# fpga.net
KiCad netlist of a schematic drawn in Altium Designer
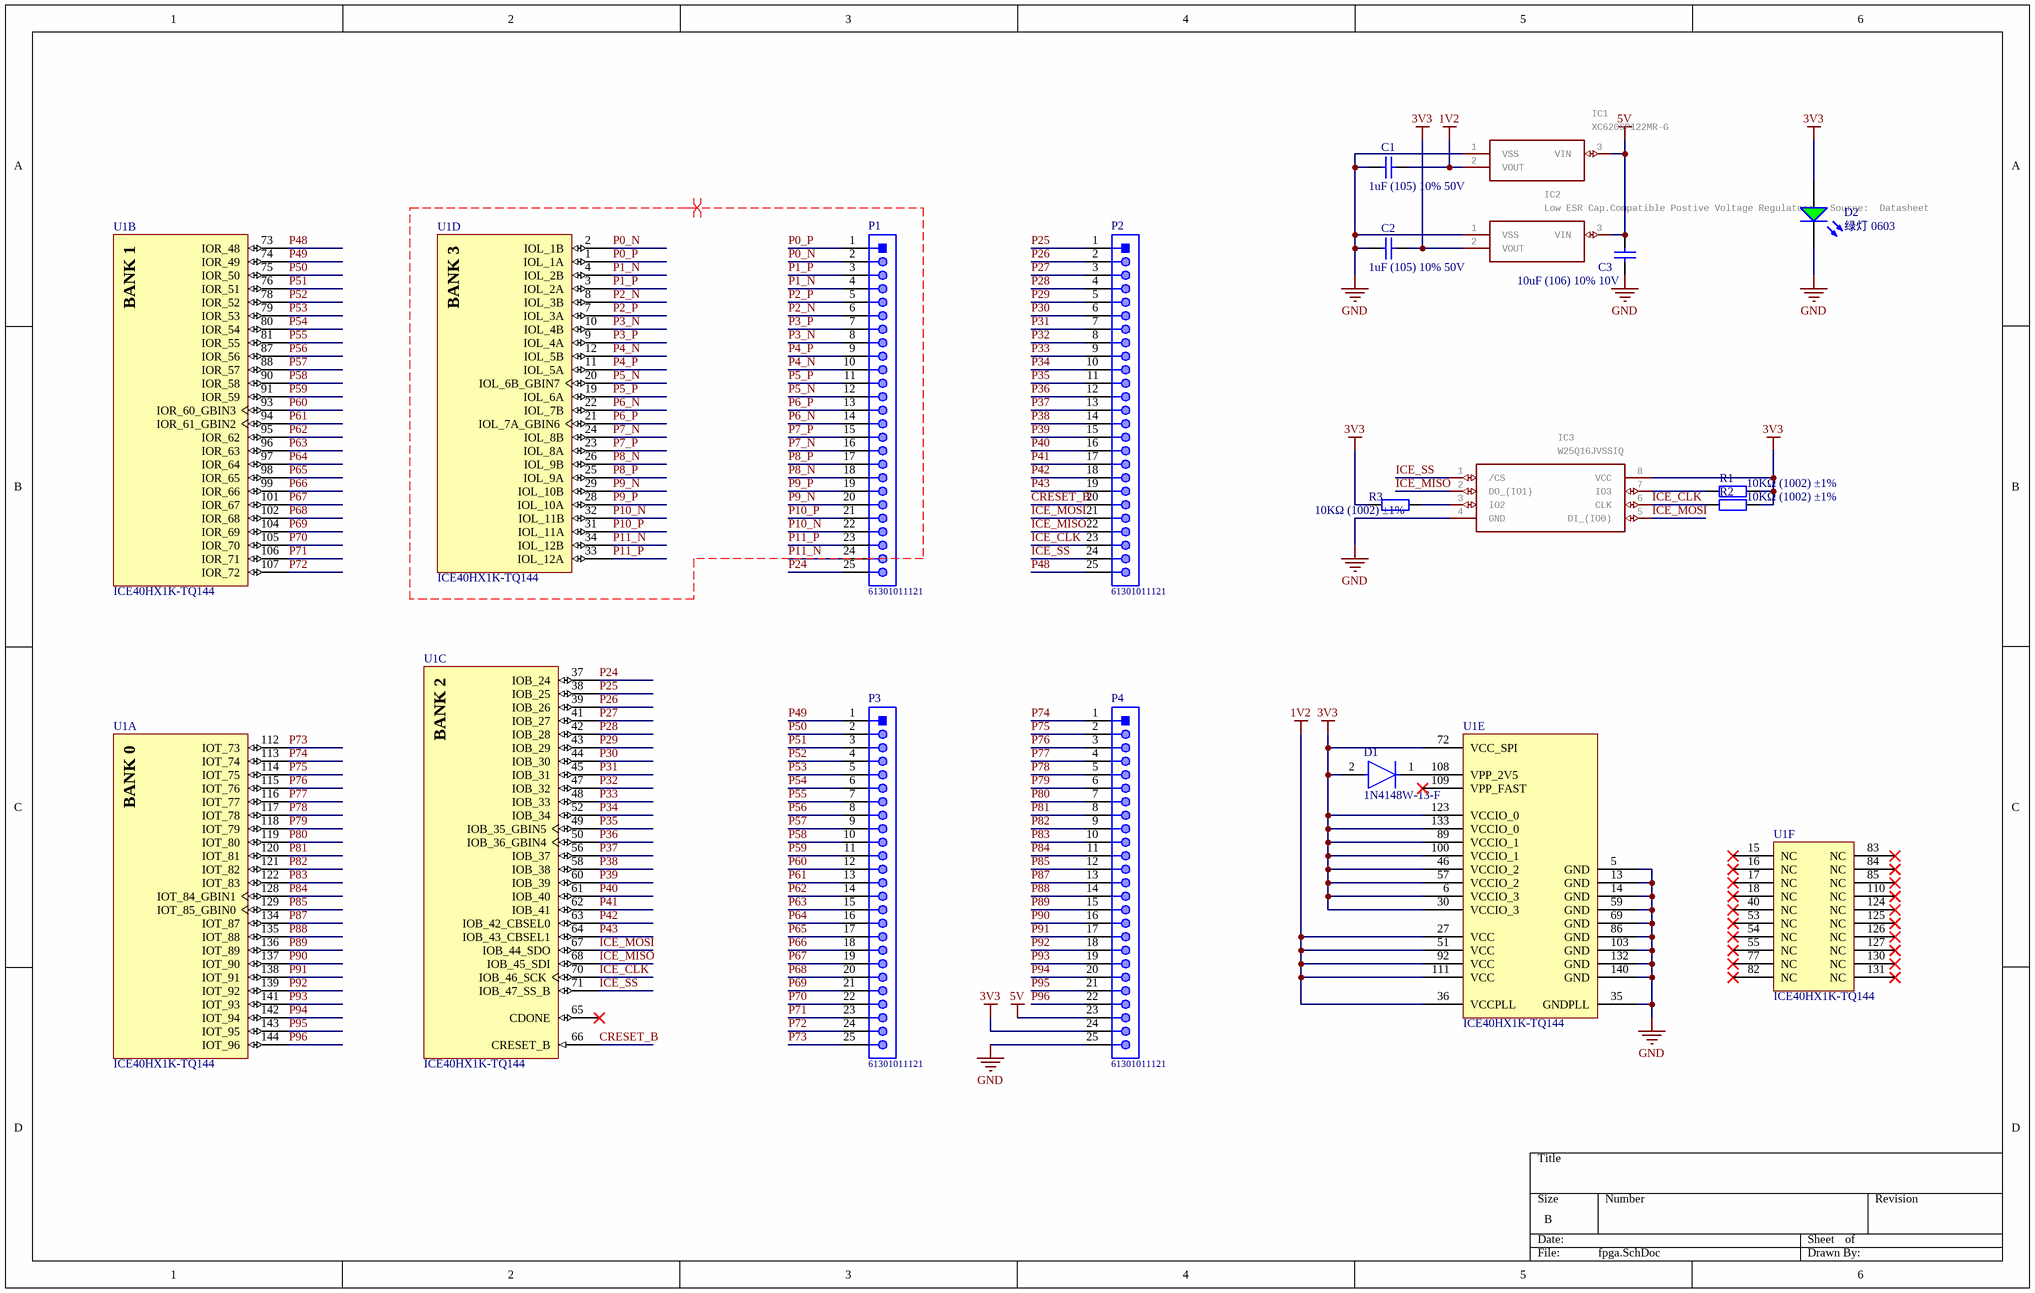
[diagram p0: fpga.SchDoc]

(export (version "E")
  (design (tool "Eeschema 10.0.6"))
  (components
    (comp (ref "C1")
      (value "1uF (105) 10% 50V")
      (footprint "0603_C")
      (description "贴片电容")
      (libsource (lib "Cap") (part "0603 1uF (105) 10% 50V"))
    )
    (comp (ref "C2")
      (value "1uF (105) 10% 50V")
      (footprint "0603_C")
      (description "贴片电容")
      (libsource (lib "Cap") (part "0603 1uF (105) 10% 50V"))
    )
    (comp (ref "C3")
      (value "10uF (106) 10% 10V")
      (footprint "0603_C")
      (description "贴片电容")
      (libsource (lib "Cap") (part "0603 10uF (106) 10% 10V"))
    )
    (comp (ref "D1")
      (value "1N4148W-13-F")
      (footprint "FP-SOD123-MFG")
      (description "DIODE GEN PURP 100V 150MA SOD123")
      (fields
        (field (name "OCTOPART") "https://octopart.com/1n4148w-13-f-diodes+inc.-2359612")
        (field (name "MANUFACTURER") "Diodes Inc.")
      )
      (libsource (lib "Altium Content Vault") (part "d7152d700b627762746794eb795d46e"))
    )
    (comp (ref "D2")
      (value "绿灯 0603")
      (footprint "0603_LED_S1")
      (description "发光二极管")
      (libsource (lib "LED") (part "0603 绿灯"))
    )
    (comp (ref "IC1")
      (value "XC6206P122MR-G")
      (footprint "SOT95P280X130-3N")
      (fields (field (name "MOUSER_PART_NUMBER") "865-XC6206P122MR-G"))
      (libsource (lib "XC6206P122MR-G") (part "XC6206P122MR-G"))
    )
    (comp (ref "IC2")
      (value "Low ESR Cap.Compatible Postive Voltage Regulators   Source:  Datasheet")
      (footprint "SOT95P280X130-3N")
      (fields (field (name "MANUFACTURER_PART_NUMBER") "XC6206P332MR"))
      (libsource (lib "XC6206P332MR") (part "XC6206P332MR"))
    )
    (comp (ref "IC3")
      (value "W25Q16JVSSIQ")
      (footprint "SOIC127P790X216-8N")
      (fields (field (name "MOUSER_PART_NUMBER") "454-W25Q16JVSSIQ"))
      (libsource (lib "W25Q16JVSSIQ") (part "W25Q16JVSSIQ"))
    )
    (comp (ref "P1")
      (value "61301011121")
      (footprint "61301011121")
      (description "THT Vertical Pin Header WR-PHD, Pitch 2.54 mm, Single Row, 25 pins")
      (libsource (lib "headers") (part "header"))
    )
    (comp (ref "P2")
      (value "61301011121")
      (footprint "61301011121")
      (description "THT Vertical Pin Header WR-PHD, Pitch 2.54 mm, Single Row, 25 pins")
      (libsource (lib "headers") (part "header"))
    )
    (comp (ref "P3")
      (value "61301011121")
      (footprint "61301011121")
      (description "THT Vertical Pin Header WR-PHD, Pitch 2.54 mm, Single Row, 25 pins")
      (libsource (lib "headers") (part "header"))
    )
    (comp (ref "P4")
      (value "61301011121")
      (footprint "61301011121")
      (description "THT Vertical Pin Header WR-PHD, Pitch 2.54 mm, Single Row, 25 pins")
      (libsource (lib "headers") (part "header"))
    )
    (comp (ref "R1")
      (value "10KΩ (1002) ±1%")
      (footprint "0603_R")
      (description "贴片电阻")
      (libsource (lib "RES") (part "0603 10KΩ (1002) 1%"))
    )
    (comp (ref "R2")
      (value "10KΩ (1002) ±1%")
      (footprint "0603_R")
      (description "贴片电阻")
      (libsource (lib "RES") (part "0603 10KΩ (1002) 1%"))
    )
    (comp (ref "R3")
      (value "10KΩ (1002) ±1%")
      (footprint "0603_R")
      (description "贴片电阻")
      (libsource (lib "RES") (part "0603 10KΩ (1002) 1%"))
    )
    (comp (ref "U1")
      (value "ICE40HX1K-TQ144")
      (footprint "LATC-TQFP-144_L")
      (fields (field (name "MANUFACTURER") "Lattice Semiconductor"))
      (libsource (lib "Altium Content Vault") (part "LATC-HX1K-TQFP-144"))
    )
  )
  (nets
    (net (code "1") (name "/CRESET_B") (class "Default")
      (node (ref "P2") (pin "20") (pinfunction "20_20") (pintype "passive"))
      (node (ref "U1") (pin "66") (pinfunction "CRESET_B_66") (pintype "input"))
    )
    (net (code "2") (name "/ICE_CLK") (class "Default")
      (node (ref "IC3") (pin "6") (pinfunction "CLK_6") (pintype "bidirectional"))
      (node (ref "P2") (pin "23") (pinfunction "23_23") (pintype "passive"))
      (node (ref "R2") (pin "1") (pinfunction "1_1") (pintype "passive"))
      (node (ref "U1") (pin "70") (pinfunction "IOB_46_SCK_70") (pintype "bidirectional"))
    )
    (net (code "3") (name "/ICE_MISO") (class "Default")
      (node (ref "IC3") (pin "2") (pinfunction "DO_(IO1)_2") (pintype "bidirectional"))
      (node (ref "P2") (pin "22") (pinfunction "22_22") (pintype "passive"))
      (node (ref "U1") (pin "68") (pinfunction "IOB_45_SDI_68") (pintype "bidirectional"))
    )
    (net (code "4") (name "/ICE_MOSI") (class "Default")
      (node (ref "IC3") (pin "5") (pinfunction "DI_(IO0)_5") (pintype "bidirectional"))
      (node (ref "P2") (pin "21") (pinfunction "21_21") (pintype "passive"))
      (node (ref "U1") (pin "67") (pinfunction "IOB_44_SDO_67") (pintype "bidirectional"))
    )
    (net (code "5") (name "/ICE_SS") (class "Default")
      (node (ref "IC3") (pin "1") (pinfunction "/CS_1") (pintype "bidirectional"))
      (node (ref "P2") (pin "24") (pinfunction "24_24") (pintype "passive"))
      (node (ref "U1") (pin "71") (pinfunction "IOB_47_SS_B_71") (pintype "bidirectional"))
    )
    (net (code "6") (name "/P0_N") (class "Default")
      (node (ref "P1") (pin "2") (pinfunction "2_2") (pintype "passive"))
      (node (ref "U1") (pin "2") (pinfunction "IOL_1B_2") (pintype "bidirectional"))
    )
    (net (code "7") (name "/P0_P") (class "Default")
      (node (ref "P1") (pin "1") (pinfunction "1_1") (pintype "passive"))
      (node (ref "U1") (pin "1") (pinfunction "IOL_1A_1") (pintype "bidirectional"))
    )
    (net (code "8") (name "/P1_N") (class "Default")
      (node (ref "P1") (pin "4") (pinfunction "4_4") (pintype "passive"))
      (node (ref "U1") (pin "4") (pinfunction "IOL_2B_4") (pintype "bidirectional"))
    )
    (net (code "9") (name "/P1_P") (class "Default")
      (node (ref "P1") (pin "3") (pinfunction "3_3") (pintype "passive"))
      (node (ref "U1") (pin "3") (pinfunction "IOL_2A_3") (pintype "bidirectional"))
    )
    (net (code "10") (name "/P2_N") (class "Default")
      (node (ref "P1") (pin "6") (pinfunction "6_6") (pintype "passive"))
      (node (ref "U1") (pin "8") (pinfunction "IOL_3B_8") (pintype "bidirectional"))
    )
    (net (code "11") (name "/P2_P") (class "Default")
      (node (ref "P1") (pin "5") (pinfunction "5_5") (pintype "passive"))
      (node (ref "U1") (pin "7") (pinfunction "IOL_3A_7") (pintype "bidirectional"))
    )
    (net (code "12") (name "/P3_N") (class "Default")
      (node (ref "P1") (pin "8") (pinfunction "8_8") (pintype "passive"))
      (node (ref "U1") (pin "10") (pinfunction "IOL_4B_10") (pintype "bidirectional"))
    )
    (net (code "13") (name "/P3_P") (class "Default")
      (node (ref "P1") (pin "7") (pinfunction "7_7") (pintype "passive"))
      (node (ref "U1") (pin "9") (pinfunction "IOL_4A_9") (pintype "bidirectional"))
    )
    (net (code "14") (name "/P4_N") (class "Default")
      (node (ref "P1") (pin "10") (pinfunction "10_10") (pintype "passive"))
      (node (ref "U1") (pin "12") (pinfunction "IOL_5B_12") (pintype "bidirectional"))
    )
    (net (code "15") (name "/P4_P") (class "Default")
      (node (ref "P1") (pin "9") (pinfunction "9_9") (pintype "passive"))
      (node (ref "U1") (pin "11") (pinfunction "IOL_5A_11") (pintype "bidirectional"))
    )
    (net (code "16") (name "/P5_N") (class "Default")
      (node (ref "P1") (pin "12") (pinfunction "12_12") (pintype "passive"))
      (node (ref "U1") (pin "20") (pinfunction "IOL_6B_GBIN7_20") (pintype "bidirectional"))
    )
    (net (code "17") (name "/P5_P") (class "Default")
      (node (ref "P1") (pin "11") (pinfunction "11_11") (pintype "passive"))
      (node (ref "U1") (pin "19") (pinfunction "IOL_6A_19") (pintype "bidirectional"))
    )
    (net (code "18") (name "/P6_N") (class "Default")
      (node (ref "P1") (pin "14") (pinfunction "14_14") (pintype "passive"))
      (node (ref "U1") (pin "22") (pinfunction "IOL_7B_22") (pintype "bidirectional"))
    )
    (net (code "19") (name "/P6_P") (class "Default")
      (node (ref "P1") (pin "13") (pinfunction "13_13") (pintype "passive"))
      (node (ref "U1") (pin "21") (pinfunction "IOL_7A_GBIN6_21") (pintype "bidirectional"))
    )
    (net (code "20") (name "/P7_N") (class "Default")
      (node (ref "P1") (pin "16") (pinfunction "16_16") (pintype "passive"))
      (node (ref "U1") (pin "24") (pinfunction "IOL_8B_24") (pintype "bidirectional"))
    )
    (net (code "21") (name "/P7_P") (class "Default")
      (node (ref "P1") (pin "15") (pinfunction "15_15") (pintype "passive"))
      (node (ref "U1") (pin "23") (pinfunction "IOL_8A_23") (pintype "bidirectional"))
    )
    (net (code "22") (name "/P8_N") (class "Default")
      (node (ref "P1") (pin "18") (pinfunction "18_18") (pintype "passive"))
      (node (ref "U1") (pin "26") (pinfunction "IOL_9B_26") (pintype "bidirectional"))
    )
    (net (code "23") (name "/P8_P") (class "Default")
      (node (ref "P1") (pin "17") (pinfunction "17_17") (pintype "passive"))
      (node (ref "U1") (pin "25") (pinfunction "IOL_9A_25") (pintype "bidirectional"))
    )
    (net (code "24") (name "/P9_N") (class "Default")
      (node (ref "P1") (pin "20") (pinfunction "20_20") (pintype "passive"))
      (node (ref "U1") (pin "29") (pinfunction "IOL_10B_29") (pintype "bidirectional"))
    )
    (net (code "25") (name "/P9_P") (class "Default")
      (node (ref "P1") (pin "19") (pinfunction "19_19") (pintype "passive"))
      (node (ref "U1") (pin "28") (pinfunction "IOL_10A_28") (pintype "bidirectional"))
    )
    (net (code "26") (name "/P10_N") (class "Default")
      (node (ref "P1") (pin "22") (pinfunction "22_22") (pintype "passive"))
      (node (ref "U1") (pin "32") (pinfunction "IOL_11B_32") (pintype "bidirectional"))
    )
    (net (code "27") (name "/P10_P") (class "Default")
      (node (ref "P1") (pin "21") (pinfunction "21_21") (pintype "passive"))
      (node (ref "U1") (pin "31") (pinfunction "IOL_11A_31") (pintype "bidirectional"))
    )
    (net (code "28") (name "/P11_N") (class "Default")
      (node (ref "P1") (pin "24") (pinfunction "24_24") (pintype "passive"))
      (node (ref "U1") (pin "34") (pinfunction "IOL_12B_34") (pintype "bidirectional"))
    )
    (net (code "29") (name "/P11_P") (class "Default")
      (node (ref "P1") (pin "23") (pinfunction "23_23") (pintype "passive"))
      (node (ref "U1") (pin "33") (pinfunction "IOL_12A_33") (pintype "bidirectional"))
    )
    (net (code "30") (name "/P24") (class "Default")
      (node (ref "P1") (pin "25") (pinfunction "25_25") (pintype "passive"))
      (node (ref "U1") (pin "37") (pinfunction "IOB_24_37") (pintype "bidirectional"))
    )
    (net (code "31") (name "/P25") (class "Default")
      (node (ref "P2") (pin "1") (pinfunction "1_1") (pintype "passive"))
      (node (ref "U1") (pin "38") (pinfunction "IOB_25_38") (pintype "bidirectional"))
    )
    (net (code "32") (name "/P26") (class "Default")
      (node (ref "P2") (pin "2") (pinfunction "2_2") (pintype "passive"))
      (node (ref "U1") (pin "39") (pinfunction "IOB_26_39") (pintype "bidirectional"))
    )
    (net (code "33") (name "/P27") (class "Default")
      (node (ref "P2") (pin "3") (pinfunction "3_3") (pintype "passive"))
      (node (ref "U1") (pin "41") (pinfunction "IOB_27_41") (pintype "bidirectional"))
    )
    (net (code "34") (name "/P28") (class "Default")
      (node (ref "P2") (pin "4") (pinfunction "4_4") (pintype "passive"))
      (node (ref "U1") (pin "42") (pinfunction "IOB_28_42") (pintype "bidirectional"))
    )
    (net (code "35") (name "/P29") (class "Default")
      (node (ref "P2") (pin "5") (pinfunction "5_5") (pintype "passive"))
      (node (ref "U1") (pin "43") (pinfunction "IOB_29_43") (pintype "bidirectional"))
    )
    (net (code "36") (name "/P30") (class "Default")
      (node (ref "P2") (pin "6") (pinfunction "6_6") (pintype "passive"))
      (node (ref "U1") (pin "44") (pinfunction "IOB_30_44") (pintype "bidirectional"))
    )
    (net (code "37") (name "/P31") (class "Default")
      (node (ref "P2") (pin "7") (pinfunction "7_7") (pintype "passive"))
      (node (ref "U1") (pin "45") (pinfunction "IOB_31_45") (pintype "bidirectional"))
    )
    (net (code "38") (name "/P32") (class "Default")
      (node (ref "P2") (pin "8") (pinfunction "8_8") (pintype "passive"))
      (node (ref "U1") (pin "47") (pinfunction "IOB_32_47") (pintype "bidirectional"))
    )
    (net (code "39") (name "/P33") (class "Default")
      (node (ref "P2") (pin "9") (pinfunction "9_9") (pintype "passive"))
      (node (ref "U1") (pin "48") (pinfunction "IOB_33_48") (pintype "bidirectional"))
    )
    (net (code "40") (name "/P34") (class "Default")
      (node (ref "P2") (pin "10") (pinfunction "10_10") (pintype "passive"))
      (node (ref "U1") (pin "52") (pinfunction "IOB_34_52") (pintype "bidirectional"))
    )
    (net (code "41") (name "/P35") (class "Default")
      (node (ref "P2") (pin "11") (pinfunction "11_11") (pintype "passive"))
      (node (ref "U1") (pin "49") (pinfunction "IOB_35_GBIN5_49") (pintype "bidirectional"))
    )
    (net (code "42") (name "/P36") (class "Default")
      (node (ref "P2") (pin "12") (pinfunction "12_12") (pintype "passive"))
      (node (ref "U1") (pin "50") (pinfunction "IOB_36_GBIN4_50") (pintype "bidirectional"))
    )
    (net (code "43") (name "/P37") (class "Default")
      (node (ref "P2") (pin "13") (pinfunction "13_13") (pintype "passive"))
      (node (ref "U1") (pin "56") (pinfunction "IOB_37_56") (pintype "bidirectional"))
    )
    (net (code "44") (name "/P38") (class "Default")
      (node (ref "P2") (pin "14") (pinfunction "14_14") (pintype "passive"))
      (node (ref "U1") (pin "58") (pinfunction "IOB_38_58") (pintype "bidirectional"))
    )
    (net (code "45") (name "/P39") (class "Default")
      (node (ref "P2") (pin "15") (pinfunction "15_15") (pintype "passive"))
      (node (ref "U1") (pin "60") (pinfunction "IOB_39_60") (pintype "bidirectional"))
    )
    (net (code "46") (name "/P40") (class "Default")
      (node (ref "P2") (pin "16") (pinfunction "16_16") (pintype "passive"))
      (node (ref "U1") (pin "61") (pinfunction "IOB_40_61") (pintype "bidirectional"))
    )
    (net (code "47") (name "/P41") (class "Default")
      (node (ref "P2") (pin "17") (pinfunction "17_17") (pintype "passive"))
      (node (ref "U1") (pin "62") (pinfunction "IOB_41_62") (pintype "bidirectional"))
    )
    (net (code "48") (name "/P42") (class "Default")
      (node (ref "P2") (pin "18") (pinfunction "18_18") (pintype "passive"))
      (node (ref "U1") (pin "63") (pinfunction "IOB_42_CBSEL0_63") (pintype "bidirectional"))
    )
    (net (code "49") (name "/P43") (class "Default")
      (node (ref "P2") (pin "19") (pinfunction "19_19") (pintype "passive"))
      (node (ref "U1") (pin "64") (pinfunction "IOB_43_CBSEL1_64") (pintype "bidirectional"))
    )
    (net (code "50") (name "/P48") (class "Default")
      (node (ref "P2") (pin "25") (pinfunction "25_25") (pintype "passive"))
      (node (ref "U1") (pin "73") (pinfunction "IOR_48_73") (pintype "bidirectional"))
    )
    (net (code "51") (name "/P49") (class "Default")
      (node (ref "P3") (pin "1") (pinfunction "1_1") (pintype "passive"))
      (node (ref "U1") (pin "74") (pinfunction "IOR_49_74") (pintype "bidirectional"))
    )
    (net (code "52") (name "/P50") (class "Default")
      (node (ref "P3") (pin "2") (pinfunction "2_2") (pintype "passive"))
      (node (ref "U1") (pin "75") (pinfunction "IOR_50_75") (pintype "bidirectional"))
    )
    (net (code "53") (name "/P51") (class "Default")
      (node (ref "P3") (pin "3") (pinfunction "3_3") (pintype "passive"))
      (node (ref "U1") (pin "76") (pinfunction "IOR_51_76") (pintype "bidirectional"))
    )
    (net (code "54") (name "/P52") (class "Default")
      (node (ref "P3") (pin "4") (pinfunction "4_4") (pintype "passive"))
      (node (ref "U1") (pin "78") (pinfunction "IOR_52_78") (pintype "bidirectional"))
    )
    (net (code "55") (name "/P53") (class "Default")
      (node (ref "P3") (pin "5") (pinfunction "5_5") (pintype "passive"))
      (node (ref "U1") (pin "79") (pinfunction "IOR_53_79") (pintype "bidirectional"))
    )
    (net (code "56") (name "/P54") (class "Default")
      (node (ref "P3") (pin "6") (pinfunction "6_6") (pintype "passive"))
      (node (ref "U1") (pin "80") (pinfunction "IOR_54_80") (pintype "bidirectional"))
    )
    (net (code "57") (name "/P55") (class "Default")
      (node (ref "P3") (pin "7") (pinfunction "7_7") (pintype "passive"))
      (node (ref "U1") (pin "81") (pinfunction "IOR_55_81") (pintype "bidirectional"))
    )
    (net (code "58") (name "/P56") (class "Default")
      (node (ref "P3") (pin "8") (pinfunction "8_8") (pintype "passive"))
      (node (ref "U1") (pin "87") (pinfunction "IOR_56_87") (pintype "bidirectional"))
    )
    (net (code "59") (name "/P57") (class "Default")
      (node (ref "P3") (pin "9") (pinfunction "9_9") (pintype "passive"))
      (node (ref "U1") (pin "88") (pinfunction "IOR_57_88") (pintype "bidirectional"))
    )
    (net (code "60") (name "/P58") (class "Default")
      (node (ref "P3") (pin "10") (pinfunction "10_10") (pintype "passive"))
      (node (ref "U1") (pin "90") (pinfunction "IOR_58_90") (pintype "bidirectional"))
    )
    (net (code "61") (name "/P59") (class "Default")
      (node (ref "P3") (pin "11") (pinfunction "11_11") (pintype "passive"))
      (node (ref "U1") (pin "91") (pinfunction "IOR_59_91") (pintype "bidirectional"))
    )
    (net (code "62") (name "/P60") (class "Default")
      (node (ref "P3") (pin "12") (pinfunction "12_12") (pintype "passive"))
      (node (ref "U1") (pin "93") (pinfunction "IOR_60_GBIN3_93") (pintype "bidirectional"))
    )
    (net (code "63") (name "/P61") (class "Default")
      (node (ref "P3") (pin "13") (pinfunction "13_13") (pintype "passive"))
      (node (ref "U1") (pin "94") (pinfunction "IOR_61_GBIN2_94") (pintype "bidirectional"))
    )
    (net (code "64") (name "/P62") (class "Default")
      (node (ref "P3") (pin "14") (pinfunction "14_14") (pintype "passive"))
      (node (ref "U1") (pin "95") (pinfunction "IOR_62_95") (pintype "bidirectional"))
    )
    (net (code "65") (name "/P63") (class "Default")
      (node (ref "P3") (pin "15") (pinfunction "15_15") (pintype "passive"))
      (node (ref "U1") (pin "96") (pinfunction "IOR_63_96") (pintype "bidirectional"))
    )
    (net (code "66") (name "/P64") (class "Default")
      (node (ref "P3") (pin "16") (pinfunction "16_16") (pintype "passive"))
      (node (ref "U1") (pin "97") (pinfunction "IOR_64_97") (pintype "bidirectional"))
    )
    (net (code "67") (name "/P65") (class "Default")
      (node (ref "P3") (pin "17") (pinfunction "17_17") (pintype "passive"))
      (node (ref "U1") (pin "98") (pinfunction "IOR_65_98") (pintype "bidirectional"))
    )
    (net (code "68") (name "/P66") (class "Default")
      (node (ref "P3") (pin "18") (pinfunction "18_18") (pintype "passive"))
      (node (ref "U1") (pin "99") (pinfunction "IOR_66_99") (pintype "bidirectional"))
    )
    (net (code "69") (name "/P67") (class "Default")
      (node (ref "P3") (pin "19") (pinfunction "19_19") (pintype "passive"))
      (node (ref "U1") (pin "101") (pinfunction "IOR_67_101") (pintype "bidirectional"))
    )
    (net (code "70") (name "/P68") (class "Default")
      (node (ref "P3") (pin "20") (pinfunction "20_20") (pintype "passive"))
      (node (ref "U1") (pin "102") (pinfunction "IOR_68_102") (pintype "bidirectional"))
    )
    (net (code "71") (name "/P69") (class "Default")
      (node (ref "P3") (pin "21") (pinfunction "21_21") (pintype "passive"))
      (node (ref "U1") (pin "104") (pinfunction "IOR_69_104") (pintype "bidirectional"))
    )
    (net (code "72") (name "/P70") (class "Default")
      (node (ref "P3") (pin "22") (pinfunction "22_22") (pintype "passive"))
      (node (ref "U1") (pin "105") (pinfunction "IOR_70_105") (pintype "bidirectional"))
    )
    (net (code "73") (name "/P71") (class "Default")
      (node (ref "P3") (pin "23") (pinfunction "23_23") (pintype "passive"))
      (node (ref "U1") (pin "106") (pinfunction "IOR_71_106") (pintype "bidirectional"))
    )
    (net (code "74") (name "/P72") (class "Default")
      (node (ref "P3") (pin "24") (pinfunction "24_24") (pintype "passive"))
      (node (ref "U1") (pin "107") (pinfunction "IOR_72_107") (pintype "bidirectional"))
    )
    (net (code "75") (name "/P73") (class "Default")
      (node (ref "P3") (pin "25") (pinfunction "25_25") (pintype "passive"))
      (node (ref "U1") (pin "112") (pinfunction "IOT_73_112") (pintype "bidirectional"))
    )
    (net (code "76") (name "/P74") (class "Default")
      (node (ref "P4") (pin "1") (pinfunction "1_1") (pintype "passive"))
      (node (ref "U1") (pin "113") (pinfunction "IOT_74_113") (pintype "bidirectional"))
    )
    (net (code "77") (name "/P75") (class "Default")
      (node (ref "P4") (pin "2") (pinfunction "2_2") (pintype "passive"))
      (node (ref "U1") (pin "114") (pinfunction "IOT_75_114") (pintype "bidirectional"))
    )
    (net (code "78") (name "/P76") (class "Default")
      (node (ref "P4") (pin "3") (pinfunction "3_3") (pintype "passive"))
      (node (ref "U1") (pin "115") (pinfunction "IOT_76_115") (pintype "bidirectional"))
    )
    (net (code "79") (name "/P77") (class "Default")
      (node (ref "P4") (pin "4") (pinfunction "4_4") (pintype "passive"))
      (node (ref "U1") (pin "116") (pinfunction "IOT_77_116") (pintype "bidirectional"))
    )
    (net (code "80") (name "/P78") (class "Default")
      (node (ref "P4") (pin "5") (pinfunction "5_5") (pintype "passive"))
      (node (ref "U1") (pin "117") (pinfunction "IOT_78_117") (pintype "bidirectional"))
    )
    (net (code "81") (name "/P79") (class "Default")
      (node (ref "P4") (pin "6") (pinfunction "6_6") (pintype "passive"))
      (node (ref "U1") (pin "118") (pinfunction "IOT_79_118") (pintype "bidirectional"))
    )
    (net (code "82") (name "/P80") (class "Default")
      (node (ref "P4") (pin "7") (pinfunction "7_7") (pintype "passive"))
      (node (ref "U1") (pin "119") (pinfunction "IOT_80_119") (pintype "bidirectional"))
    )
    (net (code "83") (name "/P81") (class "Default")
      (node (ref "P4") (pin "8") (pinfunction "8_8") (pintype "passive"))
      (node (ref "U1") (pin "120") (pinfunction "IOT_81_120") (pintype "bidirectional"))
    )
    (net (code "84") (name "/P82") (class "Default")
      (node (ref "P4") (pin "9") (pinfunction "9_9") (pintype "passive"))
      (node (ref "U1") (pin "121") (pinfunction "IOT_82_121") (pintype "bidirectional"))
    )
    (net (code "85") (name "/P83") (class "Default")
      (node (ref "P4") (pin "10") (pinfunction "10_10") (pintype "passive"))
      (node (ref "U1") (pin "122") (pinfunction "IOT_83_122") (pintype "bidirectional"))
    )
    (net (code "86") (name "/P84") (class "Default")
      (node (ref "P4") (pin "11") (pinfunction "11_11") (pintype "passive"))
      (node (ref "U1") (pin "128") (pinfunction "IOT_84_GBIN1_128") (pintype "bidirectional"))
    )
    (net (code "87") (name "/P85") (class "Default")
      (node (ref "P4") (pin "12") (pinfunction "12_12") (pintype "passive"))
      (node (ref "U1") (pin "129") (pinfunction "IOT_85_GBIN0_129") (pintype "bidirectional"))
    )
    (net (code "88") (name "/P87") (class "Default")
      (node (ref "P4") (pin "13") (pinfunction "13_13") (pintype "passive"))
      (node (ref "U1") (pin "134") (pinfunction "IOT_87_134") (pintype "bidirectional"))
    )
    (net (code "89") (name "/P88") (class "Default")
      (node (ref "P4") (pin "14") (pinfunction "14_14") (pintype "passive"))
      (node (ref "U1") (pin "135") (pinfunction "IOT_88_135") (pintype "bidirectional"))
    )
    (net (code "90") (name "/P89") (class "Default")
      (node (ref "P4") (pin "15") (pinfunction "15_15") (pintype "passive"))
      (node (ref "U1") (pin "136") (pinfunction "IOT_89_136") (pintype "bidirectional"))
    )
    (net (code "91") (name "/P90") (class "Default")
      (node (ref "P4") (pin "16") (pinfunction "16_16") (pintype "passive"))
      (node (ref "U1") (pin "137") (pinfunction "IOT_90_137") (pintype "bidirectional"))
    )
    (net (code "92") (name "/P91") (class "Default")
      (node (ref "P4") (pin "17") (pinfunction "17_17") (pintype "passive"))
      (node (ref "U1") (pin "138") (pinfunction "IOT_91_138") (pintype "bidirectional"))
    )
    (net (code "93") (name "/P92") (class "Default")
      (node (ref "P4") (pin "18") (pinfunction "18_18") (pintype "passive"))
      (node (ref "U1") (pin "139") (pinfunction "IOT_92_139") (pintype "bidirectional"))
    )
    (net (code "94") (name "/P93") (class "Default")
      (node (ref "P4") (pin "19") (pinfunction "19_19") (pintype "passive"))
      (node (ref "U1") (pin "141") (pinfunction "IOT_93_141") (pintype "bidirectional"))
    )
    (net (code "95") (name "/P94") (class "Default")
      (node (ref "P4") (pin "20") (pinfunction "20_20") (pintype "passive"))
      (node (ref "U1") (pin "142") (pinfunction "IOT_94_142") (pintype "bidirectional"))
    )
    (net (code "96") (name "/P95") (class "Default")
      (node (ref "P4") (pin "21") (pinfunction "21_21") (pintype "passive"))
      (node (ref "U1") (pin "143") (pinfunction "IOT_95_143") (pintype "bidirectional"))
    )
    (net (code "97") (name "/P96") (class "Default")
      (node (ref "P4") (pin "22") (pinfunction "22_22") (pintype "passive"))
      (node (ref "U1") (pin "144") (pinfunction "IOT_96_144") (pintype "bidirectional"))
    )
    (net (code "98") (name "1V2") (class "Default")
      (node (ref "C1") (pin "1") (pinfunction "1_1") (pintype "passive"))
      (node (ref "IC1") (pin "2") (pinfunction "VOUT_2") (pintype "passive"))
      (node (ref "U1") (pin "111") (pinfunction "VCC_111") (pintype "power_in"))
      (node (ref "U1") (pin "27") (pinfunction "VCC_27") (pintype "power_in"))
      (node (ref "U1") (pin "36") (pinfunction "VCCPLL_36") (pintype "power_in"))
      (node (ref "U1") (pin "51") (pinfunction "VCC_51") (pintype "power_in"))
      (node (ref "U1") (pin "92") (pinfunction "VCC_92") (pintype "power_in"))
    )
    (net (code "99") (name "3V3") (class "Default")
      (node (ref "C2") (pin "1") (pinfunction "1_1") (pintype "passive"))
      (node (ref "D1") (pin "2") (pinfunction "A_2") (pintype "passive"))
      (node (ref "D2") (pin "A") (pinfunction "A_A") (pintype "passive"))
      (node (ref "IC2") (pin "2") (pinfunction "VOUT_2") (pintype "passive"))
      (node (ref "IC3") (pin "8") (pinfunction "VCC_8") (pintype "passive"))
      (node (ref "P4") (pin "24") (pinfunction "24_24") (pintype "passive"))
      (node (ref "R1") (pin "2") (pinfunction "2_2") (pintype "passive"))
      (node (ref "R2") (pin "2") (pinfunction "2_2") (pintype "passive"))
      (node (ref "R3") (pin "1") (pinfunction "1_1") (pintype "passive"))
      (node (ref "U1") (pin "100") (pinfunction "VCCIO_1_100") (pintype "power_in"))
      (node (ref "U1") (pin "123") (pinfunction "VCCIO_0_123") (pintype "power_in"))
      (node (ref "U1") (pin "133") (pinfunction "VCCIO_0_133") (pintype "power_in"))
      (node (ref "U1") (pin "30") (pinfunction "VCCIO_3_30") (pintype "power_in"))
      (node (ref "U1") (pin "46") (pinfunction "VCCIO_2_46") (pintype "power_in"))
      (node (ref "U1") (pin "57") (pinfunction "VCCIO_2_57") (pintype "power_in"))
      (node (ref "U1") (pin "6") (pinfunction "VCCIO_3_6") (pintype "power_in"))
      (node (ref "U1") (pin "72") (pinfunction "VCC_SPI_72") (pintype "power_in"))
      (node (ref "U1") (pin "89") (pinfunction "VCCIO_1_89") (pintype "power_in"))
    )
    (net (code "100") (name "5V") (class "Default")
      (node (ref "C3") (pin "1") (pinfunction "1_1") (pintype "passive"))
      (node (ref "IC1") (pin "3") (pinfunction "VIN_3") (pintype "bidirectional"))
      (node (ref "IC2") (pin "3") (pinfunction "VIN_3") (pintype "bidirectional"))
      (node (ref "P4") (pin "23") (pinfunction "23_23") (pintype "passive"))
    )
    (net (code "101") (name "GND") (class "Default")
      (node (ref "C1") (pin "2") (pinfunction "2_2") (pintype "passive"))
      (node (ref "C2") (pin "2") (pinfunction "2_2") (pintype "passive"))
      (node (ref "C3") (pin "2") (pinfunction "2_2") (pintype "passive"))
      (node (ref "D2") (pin "K") (pinfunction "K_K") (pintype "passive"))
      (node (ref "IC1") (pin "1") (pinfunction "VSS_1") (pintype "passive"))
      (node (ref "IC2") (pin "1") (pinfunction "VSS_1") (pintype "passive"))
      (node (ref "IC3") (pin "4") (pinfunction "GND_4") (pintype "passive"))
      (node (ref "P4") (pin "25") (pinfunction "25_25") (pintype "passive"))
      (node (ref "U1") (pin "103") (pinfunction "GND_103") (pintype "power_in"))
      (node (ref "U1") (pin "13") (pinfunction "GND_13") (pintype "power_in"))
      (node (ref "U1") (pin "132") (pinfunction "GND_132") (pintype "power_in"))
      (node (ref "U1") (pin "14") (pinfunction "GND_14") (pintype "power_in"))
      (node (ref "U1") (pin "140") (pinfunction "GND_140") (pintype "power_in"))
      (node (ref "U1") (pin "35") (pinfunction "GNDPLL_35") (pintype "power_in"))
      (node (ref "U1") (pin "5") (pinfunction "GND_5") (pintype "power_in"))
      (node (ref "U1") (pin "59") (pinfunction "GND_59") (pintype "power_in"))
      (node (ref "U1") (pin "69") (pinfunction "GND_69") (pintype "power_in"))
      (node (ref "U1") (pin "86") (pinfunction "GND_86") (pintype "power_in"))
    )
    (net (code "102") (name "Net-(D1-C)") (class "Default")
      (node (ref "D1") (pin "1") (pinfunction "C_1") (pintype "passive"))
      (node (ref "U1") (pin "108") (pinfunction "VPP_2V5_108") (pintype "power_in"))
    )
    (net (code "103") (name "Net-(IC3-IO2)") (class "Default")
      (node (ref "IC3") (pin "3") (pinfunction "IO2_3") (pintype "bidirectional"))
      (node (ref "R3") (pin "2") (pinfunction "2_2") (pintype "passive"))
    )
    (net (code "104") (name "Net-(IC3-IO3)") (class "Default")
      (node (ref "IC3") (pin "7") (pinfunction "IO3_7") (pintype "bidirectional"))
      (node (ref "R1") (pin "1") (pinfunction "1_1") (pintype "passive"))
    )
    (net (code "105") (name "unconnected-(U1C-CDONE-Pad65)") (class "Default")
      (node (ref "U1") (pin "65") (pinfunction "CDONE_65") (pintype "bidirectional+no_connect"))
    )
    (net (code "106") (name "unconnected-(U1E-VPP_FAST-Pad109)") (class "Default")
      (node (ref "U1") (pin "109") (pinfunction "VPP_FAST_109") (pintype "power_in+no_connect"))
    )
    (net (code "107") (name "unconnected-(U1F-NC-Pad15)") (class "Default")
      (node (ref "U1") (pin "15") (pinfunction "NC_15") (pintype "passive+no_connect"))
    )
    (net (code "108") (name "unconnected-(U1F-NC-Pad16)") (class "Default")
      (node (ref "U1") (pin "16") (pinfunction "NC_16") (pintype "passive+no_connect"))
    )
    (net (code "109") (name "unconnected-(U1F-NC-Pad17)") (class "Default")
      (node (ref "U1") (pin "17") (pinfunction "NC_17") (pintype "passive+no_connect"))
    )
    (net (code "110") (name "unconnected-(U1F-NC-Pad18)") (class "Default")
      (node (ref "U1") (pin "18") (pinfunction "NC_18") (pintype "passive+no_connect"))
    )
    (net (code "111") (name "unconnected-(U1F-NC-Pad40)") (class "Default")
      (node (ref "U1") (pin "40") (pinfunction "NC_40") (pintype "passive+no_connect"))
    )
    (net (code "112") (name "unconnected-(U1F-NC-Pad53)") (class "Default")
      (node (ref "U1") (pin "53") (pinfunction "NC_53") (pintype "passive+no_connect"))
    )
    (net (code "113") (name "unconnected-(U1F-NC-Pad54)") (class "Default")
      (node (ref "U1") (pin "54") (pinfunction "NC_54") (pintype "passive+no_connect"))
    )
    (net (code "114") (name "unconnected-(U1F-NC-Pad55)") (class "Default")
      (node (ref "U1") (pin "55") (pinfunction "NC_55") (pintype "passive+no_connect"))
    )
    (net (code "115") (name "unconnected-(U1F-NC-Pad77)") (class "Default")
      (node (ref "U1") (pin "77") (pinfunction "NC_77") (pintype "passive+no_connect"))
    )
    (net (code "116") (name "unconnected-(U1F-NC-Pad82)") (class "Default")
      (node (ref "U1") (pin "82") (pinfunction "NC_82") (pintype "passive+no_connect"))
    )
    (net (code "117") (name "unconnected-(U1F-NC-Pad83)") (class "Default")
      (node (ref "U1") (pin "83") (pinfunction "NC_83") (pintype "passive+no_connect"))
    )
    (net (code "118") (name "unconnected-(U1F-NC-Pad84)") (class "Default")
      (node (ref "U1") (pin "84") (pinfunction "NC_84") (pintype "passive+no_connect"))
    )
    (net (code "119") (name "unconnected-(U1F-NC-Pad85)") (class "Default")
      (node (ref "U1") (pin "85") (pinfunction "NC_85") (pintype "passive+no_connect"))
    )
    (net (code "120") (name "unconnected-(U1F-NC-Pad110)") (class "Default")
      (node (ref "U1") (pin "110") (pinfunction "NC_110") (pintype "passive+no_connect"))
    )
    (net (code "121") (name "unconnected-(U1F-NC-Pad124)") (class "Default")
      (node (ref "U1") (pin "124") (pinfunction "NC_124") (pintype "passive+no_connect"))
    )
    (net (code "122") (name "unconnected-(U1F-NC-Pad125)") (class "Default")
      (node (ref "U1") (pin "125") (pinfunction "NC_125") (pintype "passive+no_connect"))
    )
    (net (code "123") (name "unconnected-(U1F-NC-Pad126)") (class "Default")
      (node (ref "U1") (pin "126") (pinfunction "NC_126") (pintype "passive+no_connect"))
    )
    (net (code "124") (name "unconnected-(U1F-NC-Pad127)") (class "Default")
      (node (ref "U1") (pin "127") (pinfunction "NC_127") (pintype "passive+no_connect"))
    )
    (net (code "125") (name "unconnected-(U1F-NC-Pad130)") (class "Default")
      (node (ref "U1") (pin "130") (pinfunction "NC_130") (pintype "passive+no_connect"))
    )
    (net (code "126") (name "unconnected-(U1F-NC-Pad131)") (class "Default")
      (node (ref "U1") (pin "131") (pinfunction "NC_131") (pintype "passive+no_connect"))
    )
  )
)
